# FPGA_MIO.net
KiCad netlist of a schematic drawn in Altium Designer
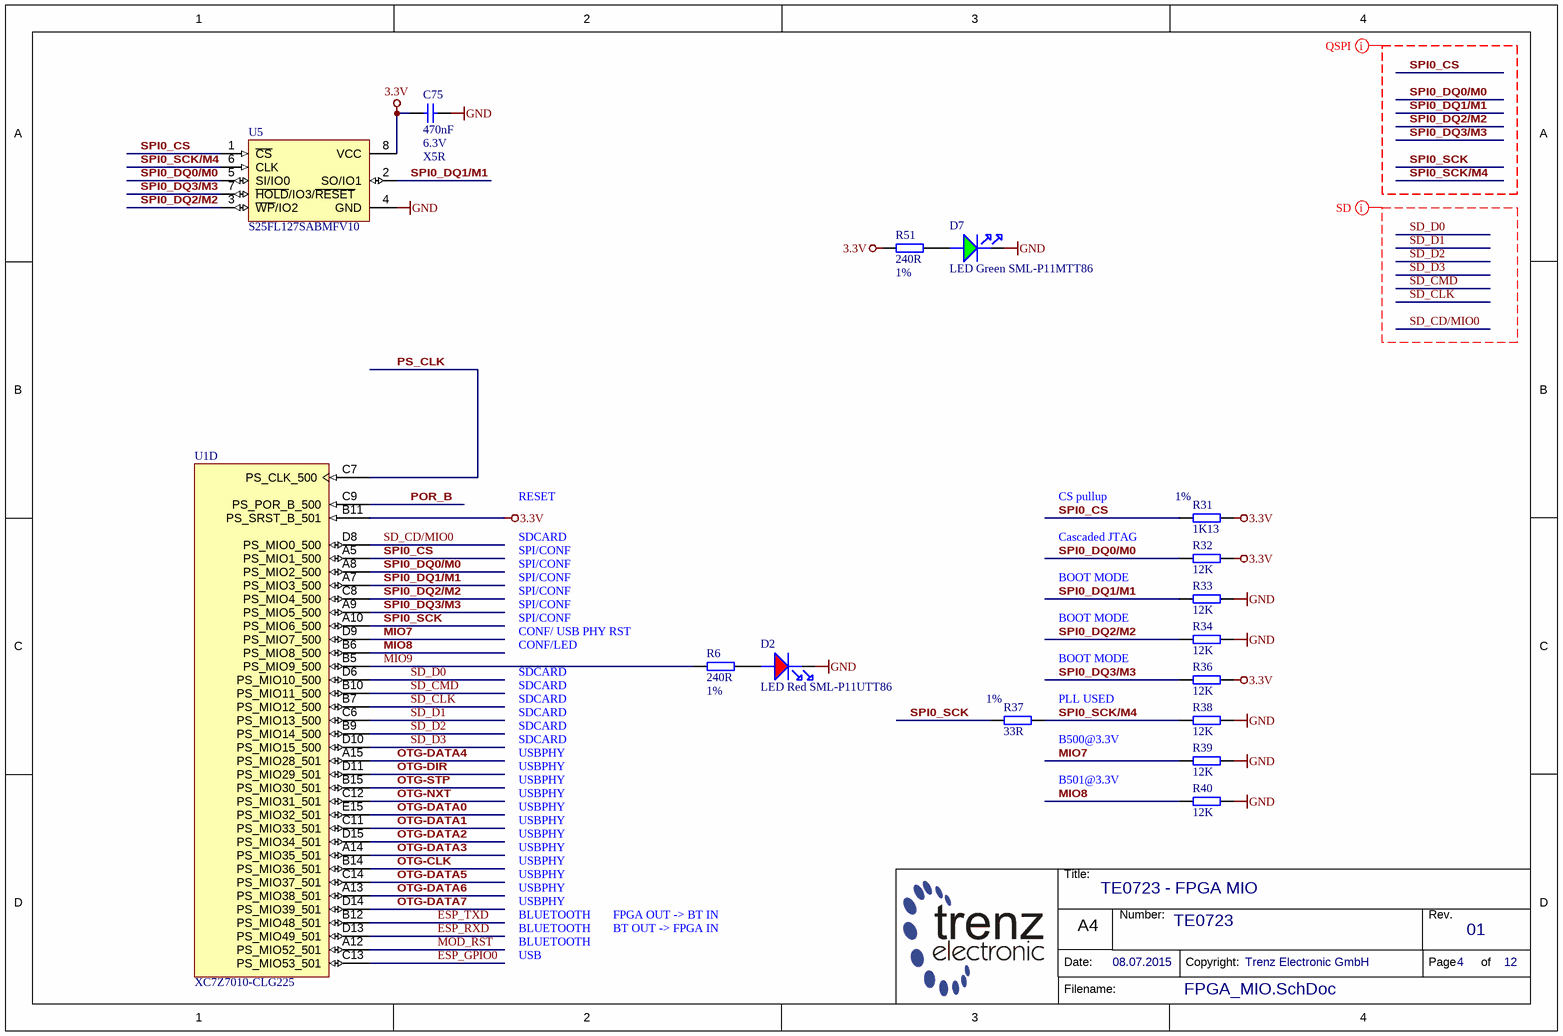
[diagram p0: FPGA_MIO.SchDoc]

(export (version "E")
  (design (tool "Eeschema 10.0.6"))
  (components
    (comp (ref "C75")
      (value "470nF")
      (footprint "CAPC0603X33N")
      (description "KON 470nF X5R 6.3V SMD 20%")
      (fields
        (field (name "VOLTAGE") "6.3V")
        (field (name "TECHNOLOGY") "X5R")
        (field (name "TOLERANCE") "20%")
      )
      (libsource (lib "TE") (part "CAP-NP"))
    )
    (comp (ref "D2")
      (value "LED Red SML-P11UTT86")
      (footprint "LEDC1006X25N_RED")
      (description "LED Rot SML-P11UTT86 SMD")
      (libsource (lib "TE") (part "LED_ROT"))
    )
    (comp (ref "D7")
      (value "LED Green SML-P11MTT86")
      (footprint "LEDC1006X25N_GREEN")
      (description "LED Grün SML-P11MTT86 SMD")
      (libsource (lib "TE") (part "LED_GRUEN"))
    )
    (comp (ref "R6")
      (value "240R")
      (footprint "RESC1005X40N")
      (description "WID SMD 240R 1% 0,063W")
      (fields (field (name "TOLERANCE") "1%"))
      (libsource (lib "TE") (part "RES"))
    )
    (comp (ref "R31")
      (value "1K13")
      (footprint "RESC1005X40N")
      (description "WID SMD 1K13 1% 0,063W")
      (fields (field (name "TOLERANCE") "1%"))
      (libsource (lib "TE") (part "RES"))
    )
    (comp (ref "R32")
      (value "12K")
      (footprint "RESC1005X40N")
      (description "WID SMD 12K 1% 0,063W")
      (libsource (lib "TE") (part "RES"))
    )
    (comp (ref "R33")
      (value "12K")
      (footprint "RESC1005X40N")
      (description "WID SMD 12K 1% 0,063W")
      (libsource (lib "TE") (part "RES"))
    )
    (comp (ref "R34")
      (value "12K")
      (footprint "RESC1005X40N")
      (description "WID SMD 12K 1% 0,063W")
      (libsource (lib "TE") (part "RES"))
    )
    (comp (ref "R36")
      (value "12K")
      (footprint "RESC1005X40N")
      (description "WID SMD 12K 1% 0,063W")
      (libsource (lib "TE") (part "RES"))
    )
    (comp (ref "R37")
      (value "33R")
      (footprint "RESC0603X26N")
      (description "WID SMD 33R 1% 0,05W")
      (fields (field (name "TOLERANCE") "1%"))
      (libsource (lib "TE") (part "RES"))
    )
    (comp (ref "R38")
      (value "12K")
      (footprint "RESC1005X40N")
      (description "WID SMD 12K 1% 0,063W")
      (libsource (lib "TE") (part "RES"))
    )
    (comp (ref "R39")
      (value "12K")
      (footprint "RESC1005X40N")
      (description "WID SMD 12K 1% 0,063W")
      (libsource (lib "TE") (part "RES"))
    )
    (comp (ref "R40")
      (value "12K")
      (footprint "RESC1005X40N")
      (description "WID SMD 12K 1% 0,063W")
      (libsource (lib "TE") (part "RES"))
    )
    (comp (ref "R51")
      (value "240R")
      (footprint "RESC1005X40N")
      (description "WID SMD 240R 1% 0,063W")
      (fields (field (name "TOLERANCE") "1%"))
      (libsource (lib "TE") (part "RES"))
    )
    (comp (ref "U1") (value "XC7Z7010-CLG225") (libsource (lib "XC7Z010-CLG225") (part "XC7Z7010-CLG225")))
    (comp (ref "U5")
      (value "S25FL127SABMFV10")
      (footprint "SOIC127P790X216-8N")
      (description "S25FL127SABMFV10 automotive SO8")
      (libsource (lib "TE") (part "S25FL127S-SO8"))
    )
  )
  (nets
    (net (code "1") (name "/ESP_GPIO0") (class "Default")
      (node (ref "U1") (pin "C13") (pinfunction "PS_MIO53_501_C13") (pintype "bidirectional"))
    )
    (net (code "2") (name "/ESP_RXD") (class "Default")
      (node (ref "U1") (pin "D13") (pinfunction "PS_MIO49_501_D13") (pintype "bidirectional"))
    )
    (net (code "3") (name "/ESP_TXD") (class "Default")
      (node (ref "U1") (pin "B12") (pinfunction "PS_MIO48_501_B12") (pintype "bidirectional"))
    )
    (net (code "4") (name "/MIO7") (class "Default")
      (node (ref "R39") (pin "1") (pinfunction "1_1") (pintype "passive"))
      (node (ref "U1") (pin "D9") (pinfunction "PS_MIO7_500_D9") (pintype "bidirectional"))
    )
    (net (code "5") (name "/MIO8") (class "Default")
      (node (ref "R40") (pin "1") (pinfunction "1_1") (pintype "passive"))
      (node (ref "U1") (pin "B6") (pinfunction "PS_MIO8_500_B6") (pintype "bidirectional"))
    )
    (net (code "6") (name "/MIO9") (class "Default")
      (node (ref "R6") (pin "2") (pinfunction "2_2") (pintype "passive"))
      (node (ref "U1") (pin "B5") (pinfunction "PS_MIO9_500_B5") (pintype "bidirectional"))
    )
    (net (code "7") (name "/MOD_RST") (class "Default")
      (node (ref "U1") (pin "A12") (pinfunction "PS_MIO52_501_A12") (pintype "bidirectional"))
    )
    (net (code "8") (name "/OTG-CLK") (class "Default")
      (node (ref "U1") (pin "B14") (pinfunction "PS_MIO36_501_B14") (pintype "bidirectional"))
    )
    (net (code "9") (name "/OTG-DATA0") (class "Default")
      (node (ref "U1") (pin "E15") (pinfunction "PS_MIO32_501_E15") (pintype "bidirectional"))
    )
    (net (code "10") (name "/OTG-DATA1") (class "Default")
      (node (ref "U1") (pin "C11") (pinfunction "PS_MIO33_501_C11") (pintype "bidirectional"))
    )
    (net (code "11") (name "/OTG-DATA2") (class "Default")
      (node (ref "U1") (pin "D15") (pinfunction "PS_MIO34_501_D15") (pintype "bidirectional"))
    )
    (net (code "12") (name "/OTG-DATA3") (class "Default")
      (node (ref "U1") (pin "A14") (pinfunction "PS_MIO35_501_A14") (pintype "bidirectional"))
    )
    (net (code "13") (name "/OTG-DATA4") (class "Default")
      (node (ref "U1") (pin "A15") (pinfunction "PS_MIO28_501_A15") (pintype "bidirectional"))
    )
    (net (code "14") (name "/OTG-DATA5") (class "Default")
      (node (ref "U1") (pin "C14") (pinfunction "PS_MIO37_501_C14") (pintype "bidirectional"))
    )
    (net (code "15") (name "/OTG-DATA6") (class "Default")
      (node (ref "U1") (pin "A13") (pinfunction "PS_MIO38_501_A13") (pintype "bidirectional"))
    )
    (net (code "16") (name "/OTG-DATA7") (class "Default")
      (node (ref "U1") (pin "D14") (pinfunction "PS_MIO39_501_D14") (pintype "bidirectional"))
    )
    (net (code "17") (name "/OTG-DIR") (class "Default")
      (node (ref "U1") (pin "D11") (pinfunction "PS_MIO29_501_D11") (pintype "bidirectional"))
    )
    (net (code "18") (name "/OTG-NXT") (class "Default")
      (node (ref "U1") (pin "C12") (pinfunction "PS_MIO31_501_C12") (pintype "bidirectional"))
    )
    (net (code "19") (name "/OTG-STP") (class "Default")
      (node (ref "U1") (pin "B15") (pinfunction "PS_MIO30_501_B15") (pintype "bidirectional"))
    )
    (net (code "20") (name "/POR_B") (class "Default")
      (node (ref "U1") (pin "C9") (pinfunction "PS_POR_B_500_C9") (pintype "input"))
    )
    (net (code "21") (name "/PS_CLK") (class "Default")
      (node (ref "U1") (pin "C7") (pinfunction "PS_CLK_500_C7") (pintype "input"))
    )
    (net (code "22") (name "/SD_CD{slash}MIO0") (class "Default")
      (node (ref "U1") (pin "D8") (pinfunction "PS_MIO0_500_D8") (pintype "bidirectional"))
    )
    (net (code "23") (name "/SD_CLK") (class "Default")
      (node (ref "U1") (pin "B7") (pinfunction "PS_MIO12_500_B7") (pintype "bidirectional"))
    )
    (net (code "24") (name "/SD_CMD") (class "Default")
      (node (ref "U1") (pin "B10") (pinfunction "PS_MIO11_500_B10") (pintype "bidirectional"))
    )
    (net (code "25") (name "/SD_D0") (class "Default")
      (node (ref "U1") (pin "D6") (pinfunction "PS_MIO10_500_D6") (pintype "bidirectional"))
    )
    (net (code "26") (name "/SD_D1") (class "Default")
      (node (ref "U1") (pin "C6") (pinfunction "PS_MIO13_500_C6") (pintype "bidirectional"))
    )
    (net (code "27") (name "/SD_D2") (class "Default")
      (node (ref "U1") (pin "B9") (pinfunction "PS_MIO14_500_B9") (pintype "bidirectional"))
    )
    (net (code "28") (name "/SD_D3") (class "Default")
      (node (ref "U1") (pin "D10") (pinfunction "PS_MIO15_500_D10") (pintype "bidirectional"))
    )
    (net (code "29") (name "/SPI0_CS") (class "Default")
      (node (ref "R31") (pin "1") (pinfunction "1_1") (pintype "passive"))
      (node (ref "U1") (pin "A5") (pinfunction "PS_MIO1_500_A5") (pintype "bidirectional"))
      (node (ref "U5") (pin "1") (pinfunction "~{CS}_1") (pintype "input"))
    )
    (net (code "30") (name "/SPI0_DQ0{slash}M0") (class "Default")
      (node (ref "R32") (pin "1") (pinfunction "1_1") (pintype "passive"))
      (node (ref "U1") (pin "A8") (pinfunction "PS_MIO2_500_A8") (pintype "bidirectional"))
      (node (ref "U5") (pin "5") (pinfunction "SI/IO0_5") (pintype "bidirectional"))
    )
    (net (code "31") (name "/SPI0_DQ1{slash}M1") (class "Default")
      (node (ref "R33") (pin "1") (pinfunction "1_1") (pintype "passive"))
      (node (ref "U1") (pin "A7") (pinfunction "PS_MIO3_500_A7") (pintype "bidirectional"))
      (node (ref "U5") (pin "2") (pinfunction "SO/IO1_2") (pintype "bidirectional"))
    )
    (net (code "32") (name "/SPI0_DQ2{slash}M2") (class "Default")
      (node (ref "R34") (pin "1") (pinfunction "1_1") (pintype "passive"))
      (node (ref "U1") (pin "C8") (pinfunction "PS_MIO4_500_C8") (pintype "bidirectional"))
      (node (ref "U5") (pin "3") (pinfunction "~{WP}/IO2_3") (pintype "bidirectional"))
    )
    (net (code "33") (name "/SPI0_DQ3{slash}M3") (class "Default")
      (node (ref "R36") (pin "1") (pinfunction "1_1") (pintype "passive"))
      (node (ref "U1") (pin "A9") (pinfunction "PS_MIO5_500_A9") (pintype "bidirectional"))
      (node (ref "U5") (pin "7") (pinfunction "~{HOLD}/IO3/~{RESET}_7") (pintype "bidirectional"))
    )
    (net (code "34") (name "/SPI0_SCK") (class "Default")
      (node (ref "R37") (pin "1") (pinfunction "1_1") (pintype "passive"))
      (node (ref "U1") (pin "A10") (pinfunction "PS_MIO6_500_A10") (pintype "bidirectional"))
    )
    (net (code "35") (name "/SPI0_SCK{slash}M4") (class "Default")
      (node (ref "R37") (pin "2") (pinfunction "2_2") (pintype "passive"))
      (node (ref "R38") (pin "1") (pinfunction "1_1") (pintype "passive"))
      (node (ref "U5") (pin "6") (pinfunction "CLK_6") (pintype "input"))
    )
    (net (code "36") (name "3.3V") (class "Default")
      (node (ref "C75") (pin "1") (pinfunction "1_1") (pintype "passive"))
      (node (ref "R31") (pin "2") (pinfunction "2_2") (pintype "passive"))
      (node (ref "R32") (pin "2") (pinfunction "2_2") (pintype "passive"))
      (node (ref "R36") (pin "2") (pinfunction "2_2") (pintype "passive"))
      (node (ref "R51") (pin "2") (pinfunction "2_2") (pintype "passive"))
      (node (ref "U1") (pin "B11") (pinfunction "PS_SRST_B_501_B11") (pintype "input"))
      (node (ref "U5") (pin "8") (pinfunction "VCC_8") (pintype "power_in"))
    )
    (net (code "37") (name "GND") (class "Default")
      (node (ref "C75") (pin "2") (pinfunction "2_2") (pintype "passive"))
      (node (ref "D2") (pin "K") (pinfunction "K_K") (pintype "passive"))
      (node (ref "D7") (pin "K") (pinfunction "K_K") (pintype "passive"))
      (node (ref "R33") (pin "2") (pinfunction "2_2") (pintype "passive"))
      (node (ref "R34") (pin "2") (pinfunction "2_2") (pintype "passive"))
      (node (ref "R38") (pin "2") (pinfunction "2_2") (pintype "passive"))
      (node (ref "R39") (pin "2") (pinfunction "2_2") (pintype "passive"))
      (node (ref "R40") (pin "2") (pinfunction "2_2") (pintype "passive"))
      (node (ref "U5") (pin "4") (pinfunction "GND_4") (pintype "power_in"))
    )
    (net (code "38") (name "Net-(D2-PadA)") (class "Default")
      (node (ref "D2") (pin "A") (pinfunction "A_A") (pintype "passive"))
      (node (ref "R6") (pin "1") (pinfunction "1_1") (pintype "passive"))
    )
    (net (code "39") (name "Net-(D7-PadA)") (class "Default")
      (node (ref "D7") (pin "A") (pinfunction "A_A") (pintype "passive"))
      (node (ref "R51") (pin "1") (pinfunction "1_1") (pintype "passive"))
    )
  )
)
